# Acondicionamiento_Presion.net
KiCad netlist of a schematic drawn in Altium Designer
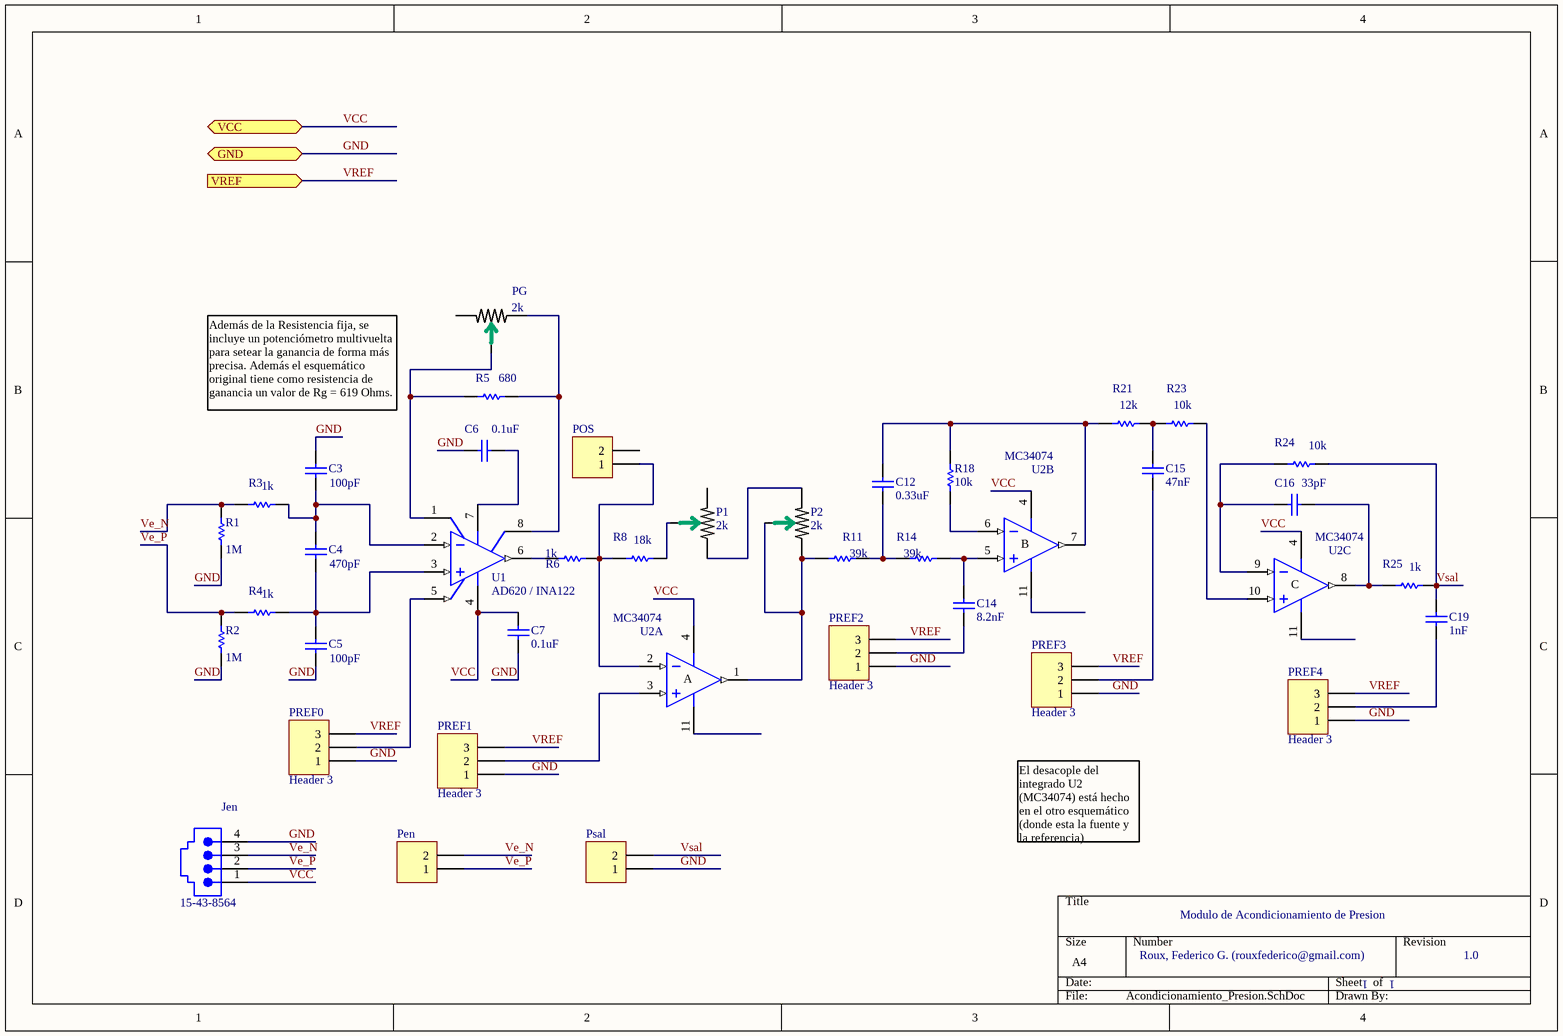
[diagram p0: Acondicionamiento_Presion.SchDoc]

(export (version "E")
  (design (tool "Eeschema 10.0.6"))
  (components
    (comp (ref "C3")
      (value "100pF")
      (footprint "6-0805_M")
      (description "Capacitor")
      (fields (field (name "Comment") "Cap") (field (name "PUBLISHER") "Altium Limited"))
      (libsource (lib "Miscellaneous Devices") (part "Cap"))
    )
    (comp (ref "C4")
      (value "470pF")
      (footprint "6-0805_M")
      (description "Capacitor")
      (fields (field (name "Comment") "Cap") (field (name "PUBLISHER") "Altium Limited"))
      (libsource (lib "Miscellaneous Devices") (part "Cap"))
    )
    (comp (ref "C5")
      (value "100pF")
      (footprint "6-0805_M")
      (description "Capacitor")
      (fields (field (name "Comment") "Cap") (field (name "PUBLISHER") "Altium Limited"))
      (libsource (lib "Miscellaneous Devices") (part "Cap"))
    )
    (comp (ref "C6")
      (value "0.1uF")
      (footprint "6-0805_M")
      (description "Capacitor")
      (fields (field (name "Comment") "Cap") (field (name "PUBLISHER") "Altium Limited"))
      (libsource (lib "Miscellaneous Devices") (part "Cap"))
    )
    (comp (ref "C7")
      (value "0.1uF")
      (footprint "6-0805_M")
      (description "Capacitor")
      (fields (field (name "Comment") "Cap") (field (name "PUBLISHER") "Altium Limited"))
      (libsource (lib "Miscellaneous Devices") (part "Cap"))
    )
    (comp (ref "C12")
      (value "0.33uF")
      (footprint "6-0805_M")
      (description "Capacitor")
      (fields (field (name "Comment") "Cap") (field (name "PUBLISHER") "Altium Limited"))
      (libsource (lib "Miscellaneous Devices") (part "Cap"))
    )
    (comp (ref "C14")
      (value "8.2nF")
      (footprint "6-0805_M")
      (description "Capacitor")
      (fields (field (name "Comment") "Cap") (field (name "PUBLISHER") "Altium Limited"))
      (libsource (lib "Miscellaneous Devices") (part "Cap"))
    )
    (comp (ref "C15")
      (value "47nF")
      (footprint "6-0805_M")
      (description "Capacitor")
      (fields (field (name "Comment") "Cap") (field (name "PUBLISHER") "Altium Limited"))
      (libsource (lib "Miscellaneous Devices") (part "Cap"))
    )
    (comp (ref "C16")
      (value "33pF")
      (footprint "6-0805_M")
      (description "Capacitor")
      (fields (field (name "Comment") "Cap") (field (name "PUBLISHER") "Altium Limited"))
      (libsource (lib "Miscellaneous Devices") (part "Cap"))
    )
    (comp (ref "C19")
      (value "1nF")
      (footprint "6-0805_M")
      (description "Capacitor")
      (fields (field (name "Comment") "Cap") (field (name "PUBLISHER") "Altium Limited"))
      (libsource (lib "Miscellaneous Devices") (part "Cap"))
    )
    (comp (ref "Jen")
      (value "15-43-8564")
      (footprint "15-43-8564")
      (description "Right Angle, Standard Profile, Unshielded PCB Jack")
      (fields (field (name "PUBLISHER") "Altium Limited"))
      (libsource (lib "Molex Modular Jack Right Angle") (part "15-43-8564"))
    )
    (comp (ref "P1")
      (value "2k")
      (footprint "Preset Largo")
      (description "Rectangular/Multiturn/Trimming Potentiometer")
      (fields
        (field (name "Comment") "Preset")
        (field (name "AUTOR") "Roux, Federico G.")
        (field (name "MAIL") "froux@favaloro.edu.ar")
      )
      (libsource (lib "Lib_Preset") (part "Preset Multivuelta"))
    )
    (comp (ref "P2")
      (value "2k")
      (footprint "Preset Largo")
      (description "Rectangular/Multiturn/Trimming Potentiometer")
      (fields
        (field (name "Comment") "Preset")
        (field (name "AUTOR") "Roux, Federico G.")
        (field (name "MAIL") "froux@favaloro.edu.ar")
      )
      (libsource (lib "Lib_Preset") (part "Preset Multivuelta"))
    )
    (comp (ref "Pen")
      (value "Header 2")
      (footprint "HDR1X2")
      (description "Header, 2-Pin")
      (fields (field (name "PUBLISHER") "Altium Limited"))
      (libsource (lib "Miscellaneous Connectors") (part "Header 2"))
    )
    (comp (ref "PG")
      (value "2k")
      (footprint "Preset Largo")
      (description "Rectangular/Multiturn/Trimming Potentiometer")
      (fields
        (field (name "Comment") "Preset")
        (field (name "AUTOR") "Roux, Federico G.")
        (field (name "MAIL") "froux@favaloro.edu.ar")
      )
      (libsource (lib "Lib_Preset") (part "Preset Multivuelta"))
    )
    (comp (ref "POS")
      (value "Header 2")
      (footprint "HDR1X2")
      (description "Header, 2-Pin")
      (fields (field (name "PUBLISHER") "Altium Limited"))
      (libsource (lib "Miscellaneous Connectors") (part "Header 2"))
    )
    (comp (ref "PREF0")
      (value "Header 3")
      (footprint "HDR1X3")
      (description "Header, 3-Pin")
      (fields (field (name "PUBLISHER") "Altium Limited"))
      (libsource (lib "Miscellaneous Connectors") (part "Header 3"))
    )
    (comp (ref "PREF1")
      (value "Header 3")
      (footprint "HDR1X3")
      (description "Header, 3-Pin")
      (fields (field (name "PUBLISHER") "Altium Limited"))
      (libsource (lib "Miscellaneous Connectors") (part "Header 3"))
    )
    (comp (ref "PREF2")
      (value "Header 3")
      (footprint "HDR1X3")
      (description "Header, 3-Pin")
      (fields (field (name "PUBLISHER") "Altium Limited"))
      (libsource (lib "Miscellaneous Connectors") (part "Header 3"))
    )
    (comp (ref "PREF3")
      (value "Header 3")
      (footprint "HDR1X3")
      (description "Header, 3-Pin")
      (fields (field (name "PUBLISHER") "Altium Limited"))
      (libsource (lib "Miscellaneous Connectors") (part "Header 3"))
    )
    (comp (ref "PREF4")
      (value "Header 3")
      (footprint "HDR1X3")
      (description "Header, 3-Pin")
      (fields (field (name "PUBLISHER") "Altium Limited"))
      (libsource (lib "Miscellaneous Connectors") (part "Header 3"))
    )
    (comp (ref "Psal")
      (value "Header 2")
      (footprint "HDR1X2")
      (description "Header, 2-Pin")
      (fields (field (name "PUBLISHER") "Altium Limited"))
      (libsource (lib "Miscellaneous Connectors") (part "Header 2"))
    )
    (comp (ref "R1")
      (value "1M")
      (footprint "6-0805_L")
      (description "Resistor")
      (fields (field (name "Comment") "Res1") (field (name "PUBLISHER") "Altium Limited"))
      (libsource (lib "Miscellaneous Devices") (part "Res1"))
    )
    (comp (ref "R2")
      (value "1M")
      (footprint "6-0805_L")
      (description "Resistor")
      (fields (field (name "Comment") "Res1") (field (name "PUBLISHER") "Altium Limited"))
      (libsource (lib "Miscellaneous Devices") (part "Res1"))
    )
    (comp (ref "R3")
      (value "1k")
      (footprint "6-0805_L")
      (description "Resistor")
      (fields (field (name "Comment") "Res1") (field (name "PUBLISHER") "Altium Limited"))
      (libsource (lib "Miscellaneous Devices") (part "Res1"))
    )
    (comp (ref "R4")
      (value "1k")
      (footprint "6-0805_L")
      (description "Resistor")
      (fields (field (name "Comment") "Res1") (field (name "PUBLISHER") "Altium Limited"))
      (libsource (lib "Miscellaneous Devices") (part "Res1"))
    )
    (comp (ref "R5")
      (value "680")
      (footprint "6-0805_L")
      (description "Resistor")
      (fields (field (name "Comment") "Res1") (field (name "PUBLISHER") "Altium Limited"))
      (libsource (lib "Miscellaneous Devices") (part "Res1"))
    )
    (comp (ref "R6")
      (value "1k")
      (footprint "6-0805_L")
      (description "Resistor")
      (fields (field (name "Comment") "Res1") (field (name "PUBLISHER") "Altium Limited"))
      (libsource (lib "Miscellaneous Devices") (part "Res1"))
    )
    (comp (ref "R8")
      (value "18k")
      (footprint "6-0805_L")
      (description "Resistor")
      (fields (field (name "Comment") "Res1") (field (name "PUBLISHER") "Altium Limited"))
      (libsource (lib "Miscellaneous Devices") (part "Res1"))
    )
    (comp (ref "R11")
      (value "39k")
      (footprint "6-0805_L")
      (description "Resistor")
      (fields (field (name "Comment") "Res1") (field (name "PUBLISHER") "Altium Limited"))
      (libsource (lib "Miscellaneous Devices") (part "Res1"))
    )
    (comp (ref "R14")
      (value "39k")
      (footprint "6-0805_L")
      (description "Resistor")
      (fields (field (name "Comment") "Res1") (field (name "PUBLISHER") "Altium Limited"))
      (libsource (lib "Miscellaneous Devices") (part "Res1"))
    )
    (comp (ref "R18")
      (value "10k")
      (footprint "6-0805_L")
      (description "Resistor")
      (fields (field (name "Comment") "Res1") (field (name "PUBLISHER") "Altium Limited"))
      (libsource (lib "Miscellaneous Devices") (part "Res1"))
    )
    (comp (ref "R21")
      (value "12k")
      (footprint "6-0805_L")
      (description "Resistor")
      (fields (field (name "Comment") "Res1") (field (name "PUBLISHER") "Altium Limited"))
      (libsource (lib "Miscellaneous Devices") (part "Res1"))
    )
    (comp (ref "R23")
      (value "10k")
      (footprint "6-0805_L")
      (description "Resistor")
      (fields (field (name "Comment") "Res1") (field (name "PUBLISHER") "Altium Limited"))
      (libsource (lib "Miscellaneous Devices") (part "Res1"))
    )
    (comp (ref "R24")
      (value "10k")
      (footprint "6-0805_L")
      (description "Resistor")
      (fields (field (name "Comment") "Res1") (field (name "PUBLISHER") "Altium Limited"))
      (libsource (lib "Miscellaneous Devices") (part "Res1"))
    )
    (comp (ref "R25")
      (value "1k")
      (footprint "6-0805_L")
      (description "Resistor")
      (fields (field (name "Comment") "Res1") (field (name "PUBLISHER") "Altium Limited"))
      (libsource (lib "Miscellaneous Devices") (part "Res1"))
    )
    (comp (ref "U1")
      (value "AD620 / INA122")
      (footprint "N-8")
      (description "Low-Cost, Low-Power Instrumentation Amplifier")
      (fields (field (name "PUBLISHER") "Altium Limited"))
      (libsource (lib "AD Instrumentation Amplifier") (part "AD620BN"))
    )
    (comp (ref "U2")
      (value "MC34074")
      (footprint "Q-14")
      (description "Quad Precision Low Cost High-Speed BiFET Operational Amplifier")
      (fields (field (name "PUBLISHER") "Altium Limited"))
      (libsource (lib "AD Operational Amplifier") (part "AD713BQ"))
    )
  )
  (nets
    (net (code "1") (name "/GND") (class "Default")
      (node (ref "C3") (pin "2") (pinfunction "2_2") (pintype "passive"))
      (node (ref "C5") (pin "1") (pinfunction "1_1") (pintype "passive"))
      (node (ref "C6") (pin "2") (pinfunction "2_2") (pintype "passive"))
      (node (ref "C7") (pin "2") (pinfunction "2_2") (pintype "passive"))
      (node (ref "Jen") (pin "4") (pinfunction "4_4") (pintype "passive"))
      (node (ref "PREF0") (pin "1") (pinfunction "1_1") (pintype "passive"))
      (node (ref "PREF1") (pin "1") (pinfunction "1_1") (pintype "passive"))
      (node (ref "PREF2") (pin "1") (pinfunction "1_1") (pintype "passive"))
      (node (ref "PREF3") (pin "1") (pinfunction "1_1") (pintype "passive"))
      (node (ref "PREF4") (pin "1") (pinfunction "1_1") (pintype "passive"))
      (node (ref "Psal") (pin "1") (pinfunction "1_1") (pintype "passive"))
      (node (ref "R1") (pin "1") (pinfunction "1_1") (pintype "passive"))
      (node (ref "R2") (pin "1") (pinfunction "1_1") (pintype "passive"))
    )
    (net (code "2") (name "/VCC") (class "Default")
      (node (ref "C7") (pin "1") (pinfunction "1_1") (pintype "passive"))
      (node (ref "Jen") (pin "1") (pinfunction "1_1") (pintype "passive"))
      (node (ref "U1") (pin "4") (pinfunction "V-_4") (pintype "power_in"))
      (node (ref "U2") (pin "4") (pinfunction "V+_4") (pintype "power_in"))
    )
    (net (code "3") (name "/VREF") (class "Default")
      (node (ref "PREF0") (pin "3") (pinfunction "3_3") (pintype "passive"))
      (node (ref "PREF1") (pin "3") (pinfunction "3_3") (pintype "passive"))
      (node (ref "PREF2") (pin "3") (pinfunction "3_3") (pintype "passive"))
      (node (ref "PREF3") (pin "3") (pinfunction "3_3") (pintype "passive"))
      (node (ref "PREF4") (pin "3") (pinfunction "3_3") (pintype "passive"))
    )
    (net (code "4") (name "/Ve_N") (class "Default")
      (node (ref "Jen") (pin "3") (pinfunction "3_3") (pintype "passive"))
      (node (ref "Pen") (pin "2") (pinfunction "2_2") (pintype "passive"))
      (node (ref "R1") (pin "2") (pinfunction "2_2") (pintype "passive"))
      (node (ref "R3") (pin "2") (pinfunction "2_2") (pintype "passive"))
    )
    (net (code "5") (name "/Ve_P") (class "Default")
      (node (ref "Jen") (pin "2") (pinfunction "2_2") (pintype "passive"))
      (node (ref "Pen") (pin "1") (pinfunction "1_1") (pintype "passive"))
      (node (ref "R2") (pin "2") (pinfunction "2_2") (pintype "passive"))
      (node (ref "R4") (pin "2") (pinfunction "2_2") (pintype "passive"))
    )
    (net (code "6") (name "/Vsal") (class "Default")
      (node (ref "C19") (pin "1") (pinfunction "1_1") (pintype "passive"))
      (node (ref "Psal") (pin "2") (pinfunction "2_2") (pintype "passive"))
      (node (ref "R24") (pin "1") (pinfunction "1_1") (pintype "passive"))
      (node (ref "R25") (pin "1") (pinfunction "1_1") (pintype "passive"))
    )
    (net (code "7") (name "Net-(C12-Pad2)") (class "Default")
      (node (ref "C12") (pin "2") (pinfunction "2_2") (pintype "passive"))
      (node (ref "R11") (pin "1") (pinfunction "1_1") (pintype "passive"))
      (node (ref "R14") (pin "2") (pinfunction "2_2") (pintype "passive"))
    )
    (net (code "8") (name "Net-(C14-Pad2)") (class "Default")
      (node (ref "C14") (pin "2") (pinfunction "2_2") (pintype "passive"))
      (node (ref "PREF2") (pin "2") (pinfunction "2_2") (pintype "passive"))
    )
    (net (code "9") (name "Net-(C15-Pad1)") (class "Default")
      (node (ref "C15") (pin "1") (pinfunction "1_1") (pintype "passive"))
      (node (ref "R21") (pin "1") (pinfunction "1_1") (pintype "passive"))
      (node (ref "R23") (pin "2") (pinfunction "2_2") (pintype "passive"))
    )
    (net (code "10") (name "Net-(C15-Pad2)") (class "Default")
      (node (ref "C15") (pin "2") (pinfunction "2_2") (pintype "passive"))
      (node (ref "PREF3") (pin "2") (pinfunction "2_2") (pintype "passive"))
    )
    (net (code "11") (name "Net-(C19-Pad2)") (class "Default")
      (node (ref "C19") (pin "2") (pinfunction "2_2") (pintype "passive"))
      (node (ref "PREF4") (pin "2") (pinfunction "2_2") (pintype "passive"))
    )
    (net (code "12") (name "Net-(P1-CCW)") (class "Default")
      (node (ref "P1") (pin "1") (pinfunction "CCW_1") (pintype "passive"))
      (node (ref "P2") (pin "3") (pinfunction "CW_3") (pintype "passive"))
    )
    (net (code "13") (name "Net-(P1-WLPER)") (class "Default")
      (node (ref "P1") (pin "2") (pinfunction "WLPER_2") (pintype "passive"))
      (node (ref "R8") (pin "1") (pinfunction "1_1") (pintype "passive"))
    )
    (net (code "14") (name "Net-(P2-CCW)") (class "Default")
      (node (ref "P2") (pin "1") (pinfunction "CCW_1") (pintype "passive"))
      (node (ref "P2") (pin "2") (pinfunction "WLPER_2") (pintype "passive"))
      (node (ref "R11") (pin "2") (pinfunction "2_2") (pintype "passive"))
      (node (ref "U2") (pin "1") (pinfunction "OUT_1") (pintype "output"))
    )
    (net (code "15") (name "Net-(PG-CCW)") (class "Default")
      (node (ref "PG") (pin "1") (pinfunction "CCW_1") (pintype "passive"))
      (node (ref "R5") (pin "1") (pinfunction "1_1") (pintype "passive"))
      (node (ref "U1") (pin "8") (pinfunction "RG_8") (pintype "passive"))
    )
    (net (code "16") (name "Net-(PG-WLPER)") (class "Default")
      (node (ref "PG") (pin "2") (pinfunction "WLPER_2") (pintype "passive"))
      (node (ref "R5") (pin "2") (pinfunction "2_2") (pintype "passive"))
      (node (ref "U1") (pin "1") (pinfunction "RG_1") (pintype "passive"))
    )
    (net (code "17") (name "Net-(U1-+IN)") (class "Default")
      (node (ref "C4") (pin "1") (pinfunction "1_1") (pintype "passive"))
      (node (ref "C5") (pin "2") (pinfunction "2_2") (pintype "passive"))
      (node (ref "R4") (pin "1") (pinfunction "1_1") (pintype "passive"))
      (node (ref "U1") (pin "3") (pinfunction "+IN_3") (pintype "input"))
    )
    (net (code "18") (name "Net-(U1--IN)") (class "Default")
      (node (ref "C3") (pin "1") (pinfunction "1_1") (pintype "passive"))
      (node (ref "C4") (pin "2") (pinfunction "2_2") (pintype "passive"))
      (node (ref "R3") (pin "1") (pinfunction "1_1") (pintype "passive"))
      (node (ref "U1") (pin "2") (pinfunction "-IN_2") (pintype "input"))
    )
    (net (code "19") (name "Net-(U1-OUT)") (class "Default")
      (node (ref "R6") (pin "2") (pinfunction "2_2") (pintype "passive"))
      (node (ref "U1") (pin "6") (pinfunction "OUT_6") (pintype "output"))
    )
    (net (code "20") (name "Net-(U1-REF)") (class "Default")
      (node (ref "PREF0") (pin "2") (pinfunction "2_2") (pintype "passive"))
      (node (ref "U1") (pin "5") (pinfunction "REF_5") (pintype "input"))
    )
    (net (code "21") (name "Net-(U1-V+)") (class "Default")
      (node (ref "C6") (pin "1") (pinfunction "1_1") (pintype "passive"))
      (node (ref "U1") (pin "7") (pinfunction "V+_7") (pintype "power_in"))
    )
    (net (code "22") (name "Net-(U2A-IN+)") (class "Default")
      (node (ref "PREF1") (pin "2") (pinfunction "2_2") (pintype "passive"))
      (node (ref "U2") (pin "3") (pinfunction "IN+_3") (pintype "input"))
    )
    (net (code "23") (name "Net-(U2A-IN-)") (class "Default")
      (node (ref "POS") (pin "1") (pinfunction "1_1") (pintype "passive"))
      (node (ref "R6") (pin "1") (pinfunction "1_1") (pintype "passive"))
      (node (ref "R8") (pin "2") (pinfunction "2_2") (pintype "passive"))
      (node (ref "U2") (pin "2") (pinfunction "IN-_2") (pintype "input"))
    )
    (net (code "24") (name "Net-(U2B-IN+)") (class "Default")
      (node (ref "C14") (pin "1") (pinfunction "1_1") (pintype "passive"))
      (node (ref "R14") (pin "1") (pinfunction "1_1") (pintype "passive"))
      (node (ref "U2") (pin "5") (pinfunction "IN+_5") (pintype "input"))
    )
    (net (code "25") (name "Net-(U2B-IN-)") (class "Default")
      (node (ref "R18") (pin "2") (pinfunction "2_2") (pintype "passive"))
      (node (ref "U2") (pin "6") (pinfunction "IN-_6") (pintype "input"))
    )
    (net (code "26") (name "Net-(U2B-OUT)") (class "Default")
      (node (ref "C12") (pin "1") (pinfunction "1_1") (pintype "passive"))
      (node (ref "R18") (pin "1") (pinfunction "1_1") (pintype "passive"))
      (node (ref "R21") (pin "2") (pinfunction "2_2") (pintype "passive"))
      (node (ref "U2") (pin "7") (pinfunction "OUT_7") (pintype "output"))
    )
    (net (code "27") (name "Net-(U2C-IN+)") (class "Default")
      (node (ref "R23") (pin "1") (pinfunction "1_1") (pintype "passive"))
      (node (ref "U2") (pin "10") (pinfunction "IN+_10") (pintype "input"))
    )
    (net (code "28") (name "Net-(U2C-IN-)") (class "Default")
      (node (ref "C16") (pin "2") (pinfunction "2_2") (pintype "passive"))
      (node (ref "R24") (pin "2") (pinfunction "2_2") (pintype "passive"))
      (node (ref "U2") (pin "9") (pinfunction "IN-_9") (pintype "input"))
    )
    (net (code "29") (name "Net-(U2C-OUT)") (class "Default")
      (node (ref "C16") (pin "1") (pinfunction "1_1") (pintype "passive"))
      (node (ref "R25") (pin "2") (pinfunction "2_2") (pintype "passive"))
      (node (ref "U2") (pin "8") (pinfunction "OUT_8") (pintype "output"))
    )
    (net (code "30") (name "unconnected-(P1-CW-Pad3)") (class "Default")
      (node (ref "P1") (pin "3") (pinfunction "CW_3") (pintype "passive"))
    )
    (net (code "31") (name "unconnected-(PG-CW-Pad3)") (class "Default")
      (node (ref "PG") (pin "3") (pinfunction "CW_3") (pintype "passive"))
    )
    (net (code "32") (name "unconnected-(POS-Pad2)") (class "Default")
      (node (ref "POS") (pin "2") (pinfunction "2_2") (pintype "passive"))
    )
    (net (code "33") (name "unconnected-(U2A-V--Pad11)") (class "Default")
      (node (ref "U2") (pin "11") (pinfunction "V-_11") (pintype "power_in"))
    )
    (net (code "34") (name "unconnected-(U2B-V--Pad11)") (class "Default")
      (node (ref "U2") (pin "11") (pinfunction "V-_11") (pintype "power_in"))
    )
    (net (code "35") (name "unconnected-(U2C-V--Pad11)") (class "Default")
      (node (ref "U2") (pin "11") (pinfunction "V-_11") (pintype "power_in"))
    )
  )
)
